# schematic.net
KiCad netlist of a schematic drawn in Altium Designer
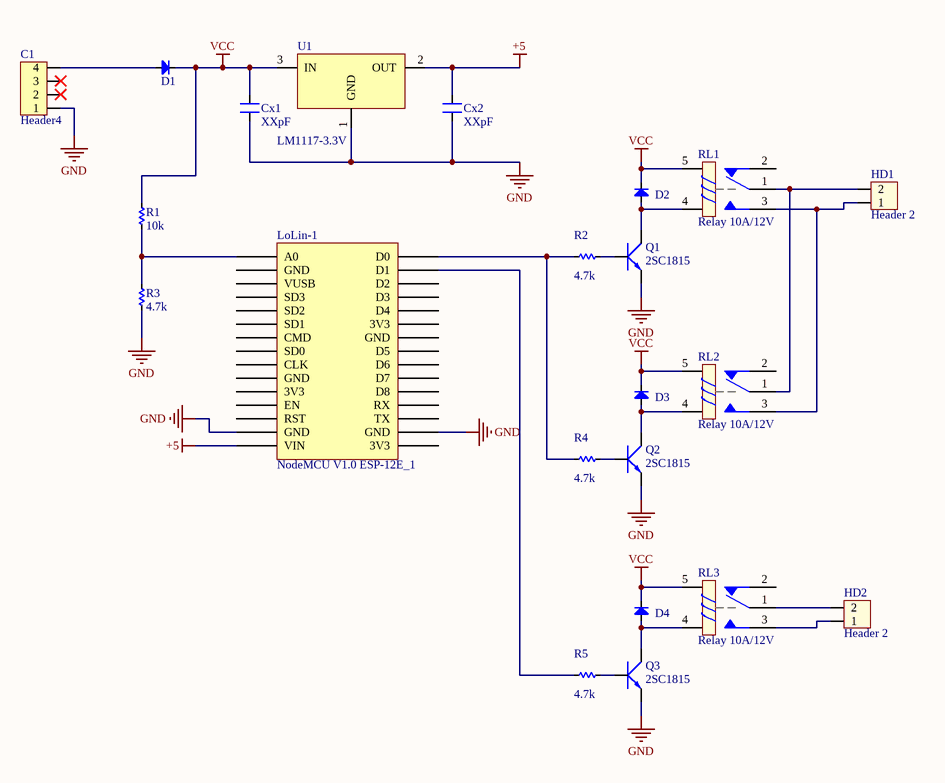
[diagram p0: schematic.SchDoc]

(export (version "E")
  (design (tool "Eeschema 10.0.6"))
  (components
    (comp (ref "C1")
      (value "Header4")
      (footprint "Header4")
      (description "Header IDC, 4 x 1 Pin Vertical 2.54mm Pitch (Non-Boxed, Male)")
      (fields
        (field (name "MANUFACTURER") "Würth Elektronik eiSos GmbH")
        (field (name "PARTNO") "613002143121")
        (field (name "CREATED BY") "Karrer Zheng")
      )
      (libsource (lib "LIBRARY") (part "Header4"))
    )
    (comp (ref "Cx1") (value "XXpF") (footprint "CN-SMD-1206") (libsource (lib "LIBRARY") (part "CN")))
    (comp (ref "Cx2") (value "XXpF") (footprint "CN-SMD-1206") (libsource (lib "LIBRARY") (part "CN")))
    (comp (ref "D1")
      (value "Diode")
      (footprint "DIO-1A-SMALL")
      (description "Default Diode")
      (fields (field (name "PUBLISHER") "Altium Limited"))
      (libsource (lib "LIBRARY") (part "Diode"))
    )
    (comp (ref "D2")
      (value "Diode")
      (footprint "DIO-1A-SMALL")
      (description "Default Diode")
      (fields (field (name "PUBLISHER") "Altium Limited"))
      (libsource (lib "LIBRARY") (part "Diode"))
    )
    (comp (ref "D3")
      (value "Diode")
      (footprint "DIO-1A-SMALL")
      (description "Default Diode")
      (fields (field (name "PUBLISHER") "Altium Limited"))
      (libsource (lib "LIBRARY") (part "Diode"))
    )
    (comp (ref "D4")
      (value "Diode")
      (footprint "DIO-1A-SMALL")
      (description "Default Diode")
      (fields (field (name "PUBLISHER") "Altium Limited"))
      (libsource (lib "LIBRARY") (part "Diode"))
    )
    (comp (ref "HD1")
      (value "Header 2")
      (footprint "HED2")
      (description "Header 2 (Green)")
      (libsource (lib "syhaunguyen") (part "Hed2"))
    )
    (comp (ref "HD2")
      (value "Header 2")
      (footprint "HED2")
      (description "Header 2 (Green)")
      (libsource (lib "syhaunguyen") (part "Hed2"))
    )
    (comp (ref "LoLin-1")
      (value "NodeMCU V1.0 ESP-12E_1")
      (footprint "LoLin NodeMcu V3")
      (description "LoLin NodeMCU V3")
      (libsource (lib "nodemcu") (part "NodeMCU V1.0 ESP-12E_1"))
    )
    (comp (ref "Q1")
      (value "2SC1815")
      (footprint "TO92-123")
      (description "NPN 600mW, ECB")
      (libsource (lib "LIBRARY") (part "2SC1815"))
    )
    (comp (ref "Q2")
      (value "2SC1815")
      (footprint "TO92-123")
      (description "NPN 600mW, ECB")
      (libsource (lib "LIBRARY") (part "2SC1815"))
    )
    (comp (ref "Q3")
      (value "2SC1815")
      (footprint "TO92-123")
      (description "NPN 600mW, ECB")
      (libsource (lib "LIBRARY") (part "2SC1815"))
    )
    (comp (ref "R1")
      (value "10k")
      (footprint "RES-1/4W-SMALL")
      (description "Res")
      (fields
        (field (name "MANUFACTURER") "Generic Components")
        (field (name "PUBLISHER") "Altium Hobart Technology Centre")
      )
      (libsource (lib "LIBRARY") (part "Res"))
    )
    (comp (ref "R2")
      (value "4.7k")
      (footprint "RES-1/4W-SMALL")
      (description "Res")
      (fields
        (field (name "MANUFACTURER") "Generic Components")
        (field (name "PUBLISHER") "Altium Hobart Technology Centre")
      )
      (libsource (lib "LIBRARY") (part "Res"))
    )
    (comp (ref "R3")
      (value "4.7k")
      (footprint "RES-1/4W-SMALL")
      (description "Res")
      (fields
        (field (name "MANUFACTURER") "Generic Components")
        (field (name "PUBLISHER") "Altium Hobart Technology Centre")
      )
      (libsource (lib "LIBRARY") (part "Res"))
    )
    (comp (ref "R4")
      (value "4.7k")
      (footprint "RES-1/4W-SMALL")
      (description "Res")
      (fields
        (field (name "MANUFACTURER") "Generic Components")
        (field (name "PUBLISHER") "Altium Hobart Technology Centre")
      )
      (libsource (lib "LIBRARY") (part "Res"))
    )
    (comp (ref "R5")
      (value "4.7k")
      (footprint "RES-1/4W-SMALL")
      (description "Res")
      (fields
        (field (name "MANUFACTURER") "Generic Components")
        (field (name "PUBLISHER") "Altium Hobart Technology Centre")
      )
      (libsource (lib "LIBRARY") (part "Res"))
    )
    (comp (ref "RL1")
      (value "Relay 10A/12V")
      (footprint "RELAY 5")
      (description "Relay SPDT,10A - 12VDC 5 Pin")
      (libsource (lib "LIBRARY") (part "Relay 5"))
    )
    (comp (ref "RL2")
      (value "Relay 10A/12V")
      (footprint "RELAY 5")
      (description "Relay SPDT,10A - 12VDC 5 Pin")
      (libsource (lib "LIBRARY") (part "Relay 5"))
    )
    (comp (ref "RL3")
      (value "Relay 10A/12V")
      (footprint "RELAY 5")
      (description "Relay SPDT,10A - 12VDC 5 Pin")
      (libsource (lib "LIBRARY") (part "Relay 5"))
    )
    (comp (ref "U1")
      (value "LM1117-3.3V")
      (footprint "SOT223")
      (description "800mA Low-Dropout Linear Regulator")
      (fields (field (name "CREATOR") "Nguyen Ba Bien"))
      (libsource (lib "LIBRARY") (part "LM1117"))
    )
  )
  (nets
    (net (code "1") (name "+5") (class "Default")
      (node (ref "Cx2") (pin "2") (pinfunction "2_2") (pintype "passive"))
      (node (ref "LoLin-1") (pin "VIN") (pinfunction "VIN_VIN") (pintype "passive"))
      (node (ref "U1") (pin "2") (pinfunction "OUT_2") (pintype "passive"))
    )
    (net (code "2") (name "GND") (class "Default")
      (node (ref "C1") (pin "1") (pinfunction "1_1") (pintype "passive"))
      (node (ref "Cx1") (pin "1") (pinfunction "1_1") (pintype "passive"))
      (node (ref "Cx2") (pin "1") (pinfunction "1_1") (pintype "passive"))
      (node (ref "LoLin-1") (pin "GND") (pinfunction "GND_GND") (pintype "passive"))
      (node (ref "Q1") (pin "1") (pinfunction "E_1") (pintype "passive"))
      (node (ref "Q2") (pin "1") (pinfunction "E_1") (pintype "passive"))
      (node (ref "Q3") (pin "1") (pinfunction "E_1") (pintype "passive"))
      (node (ref "R3") (pin "2") (pinfunction "2_2") (pintype "passive"))
      (node (ref "U1") (pin "1") (pinfunction "GND_1") (pintype "passive"))
    )
    (net (code "3") (name "Net-(D1-A)") (class "Default")
      (node (ref "C1") (pin "4") (pinfunction "4_4") (pintype "passive"))
      (node (ref "D1") (pin "1") (pinfunction "A_1") (pintype "passive"))
    )
    (net (code "4") (name "Net-(D2-A)") (class "Default")
      (node (ref "D2") (pin "1") (pinfunction "A_1") (pintype "passive"))
      (node (ref "Q1") (pin "2") (pinfunction "C_2") (pintype "passive"))
      (node (ref "RL1") (pin "4") (pinfunction "4_4") (pintype "passive"))
    )
    (net (code "5") (name "Net-(D3-A)") (class "Default")
      (node (ref "D3") (pin "1") (pinfunction "A_1") (pintype "passive"))
      (node (ref "Q2") (pin "2") (pinfunction "C_2") (pintype "passive"))
      (node (ref "RL2") (pin "4") (pinfunction "4_4") (pintype "passive"))
    )
    (net (code "6") (name "Net-(D4-A)") (class "Default")
      (node (ref "D4") (pin "1") (pinfunction "A_1") (pintype "passive"))
      (node (ref "Q3") (pin "2") (pinfunction "C_2") (pintype "passive"))
      (node (ref "RL3") (pin "4") (pinfunction "4_4") (pintype "passive"))
    )
    (net (code "7") (name "Net-(HD1-Pad1)") (class "Default")
      (node (ref "HD1") (pin "1") (pinfunction "1_1") (pintype "passive"))
      (node (ref "RL1") (pin "3") (pinfunction "3_3") (pintype "passive"))
      (node (ref "RL2") (pin "3") (pinfunction "3_3") (pintype "passive"))
    )
    (net (code "8") (name "Net-(HD1-Pad2)") (class "Default")
      (node (ref "HD1") (pin "2") (pinfunction "2_2") (pintype "passive"))
      (node (ref "RL1") (pin "1") (pinfunction "1_1") (pintype "passive"))
      (node (ref "RL2") (pin "1") (pinfunction "1_1") (pintype "passive"))
    )
    (net (code "9") (name "Net-(HD2-Pad1)") (class "Default")
      (node (ref "HD2") (pin "1") (pinfunction "1_1") (pintype "passive"))
      (node (ref "RL3") (pin "3") (pinfunction "3_3") (pintype "passive"))
    )
    (net (code "10") (name "Net-(HD2-Pad2)") (class "Default")
      (node (ref "HD2") (pin "2") (pinfunction "2_2") (pintype "passive"))
      (node (ref "RL3") (pin "1") (pinfunction "1_1") (pintype "passive"))
    )
    (net (code "11") (name "Net-(LoLin-1-PadA0)") (class "Default")
      (node (ref "LoLin-1") (pin "A0") (pinfunction "A0_A0") (pintype "passive"))
      (node (ref "R1") (pin "2") (pinfunction "2_2") (pintype "passive"))
      (node (ref "R3") (pin "1") (pinfunction "1_1") (pintype "passive"))
    )
    (net (code "12") (name "Net-(LoLin-1-PadD0)") (class "Default")
      (node (ref "LoLin-1") (pin "D0") (pinfunction "D0_D0") (pintype "passive"))
      (node (ref "R2") (pin "2") (pinfunction "2_2") (pintype "passive"))
      (node (ref "R4") (pin "2") (pinfunction "2_2") (pintype "passive"))
    )
    (net (code "13") (name "Net-(LoLin-1-PadD1)") (class "Default")
      (node (ref "LoLin-1") (pin "D1") (pinfunction "D1_D1") (pintype "passive"))
      (node (ref "R5") (pin "2") (pinfunction "2_2") (pintype "passive"))
    )
    (net (code "14") (name "Net-(Q1-B)") (class "Default")
      (node (ref "Q1") (pin "3") (pinfunction "B_3") (pintype "passive"))
      (node (ref "R2") (pin "1") (pinfunction "1_1") (pintype "passive"))
    )
    (net (code "15") (name "Net-(Q2-B)") (class "Default")
      (node (ref "Q2") (pin "3") (pinfunction "B_3") (pintype "passive"))
      (node (ref "R4") (pin "1") (pinfunction "1_1") (pintype "passive"))
    )
    (net (code "16") (name "Net-(Q3-B)") (class "Default")
      (node (ref "Q3") (pin "3") (pinfunction "B_3") (pintype "passive"))
      (node (ref "R5") (pin "1") (pinfunction "1_1") (pintype "passive"))
    )
    (net (code "17") (name "VCC") (class "Default")
      (node (ref "Cx1") (pin "2") (pinfunction "2_2") (pintype "passive"))
      (node (ref "D1") (pin "2") (pinfunction "K_2") (pintype "passive"))
      (node (ref "D2") (pin "2") (pinfunction "K_2") (pintype "passive"))
      (node (ref "D3") (pin "2") (pinfunction "K_2") (pintype "passive"))
      (node (ref "D4") (pin "2") (pinfunction "K_2") (pintype "passive"))
      (node (ref "R1") (pin "1") (pinfunction "1_1") (pintype "passive"))
      (node (ref "RL1") (pin "5") (pinfunction "5_5") (pintype "passive"))
      (node (ref "RL2") (pin "5") (pinfunction "5_5") (pintype "passive"))
      (node (ref "RL3") (pin "5") (pinfunction "5_5") (pintype "passive"))
      (node (ref "U1") (pin "3") (pinfunction "IN_3") (pintype "passive"))
    )
    (net (code "18") (name "unconnected-(C1-Pad2)") (class "Default")
      (node (ref "C1") (pin "2") (pinfunction "2_2") (pintype "passive+no_connect"))
    )
    (net (code "19") (name "unconnected-(C1-Pad3)") (class "Default")
      (node (ref "C1") (pin "3") (pinfunction "3_3") (pintype "passive+no_connect"))
    )
    (net (code "20") (name "unconnected-(LoLin-1-Pad3V3)") (class "Default")
      (node (ref "LoLin-1") (pin "3V3") (pinfunction "3V3_3V3") (pintype "passive"))
    )
    (net (code "21") (name "unconnected-(LoLin-1-Pad3V3)_1") (class "Default")
      (node (ref "LoLin-1") (pin "3V3") (pinfunction "3V3_3V3") (pintype "passive"))
    )
    (net (code "22") (name "unconnected-(LoLin-1-Pad3V3)_2") (class "Default")
      (node (ref "LoLin-1") (pin "3V3") (pinfunction "3V3_3V3") (pintype "passive"))
    )
    (net (code "23") (name "unconnected-(LoLin-1-PadCLK)") (class "Default")
      (node (ref "LoLin-1") (pin "CLK") (pinfunction "CLK_CLK") (pintype "passive"))
    )
    (net (code "24") (name "unconnected-(LoLin-1-PadCMD)") (class "Default")
      (node (ref "LoLin-1") (pin "CMD") (pinfunction "CMD_CMD") (pintype "passive"))
    )
    (net (code "25") (name "unconnected-(LoLin-1-PadD2)") (class "Default")
      (node (ref "LoLin-1") (pin "D2") (pinfunction "D2_D2") (pintype "passive"))
    )
    (net (code "26") (name "unconnected-(LoLin-1-PadD3)") (class "Default")
      (node (ref "LoLin-1") (pin "D3") (pinfunction "D3_D3") (pintype "passive"))
    )
    (net (code "27") (name "unconnected-(LoLin-1-PadD4)") (class "Default")
      (node (ref "LoLin-1") (pin "D4") (pinfunction "D4_D4") (pintype "passive"))
    )
    (net (code "28") (name "unconnected-(LoLin-1-PadD5)") (class "Default")
      (node (ref "LoLin-1") (pin "D5") (pinfunction "D5_D5") (pintype "passive"))
    )
    (net (code "29") (name "unconnected-(LoLin-1-PadD6)") (class "Default")
      (node (ref "LoLin-1") (pin "D6") (pinfunction "D6_D6") (pintype "passive"))
    )
    (net (code "30") (name "unconnected-(LoLin-1-PadD7)") (class "Default")
      (node (ref "LoLin-1") (pin "D7") (pinfunction "D7_D7") (pintype "passive"))
    )
    (net (code "31") (name "unconnected-(LoLin-1-PadD8)") (class "Default")
      (node (ref "LoLin-1") (pin "D8") (pinfunction "D8_D8") (pintype "passive"))
    )
    (net (code "32") (name "unconnected-(LoLin-1-PadEN)") (class "Default")
      (node (ref "LoLin-1") (pin "EN") (pinfunction "EN_EN") (pintype "passive"))
    )
    (net (code "33") (name "unconnected-(LoLin-1-PadGND)") (class "Default")
      (node (ref "LoLin-1") (pin "GND") (pinfunction "GND_GND") (pintype "passive"))
    )
    (net (code "34") (name "unconnected-(LoLin-1-PadGND)_1") (class "Default")
      (node (ref "LoLin-1") (pin "GND") (pinfunction "GND_GND") (pintype "passive"))
    )
    (net (code "35") (name "unconnected-(LoLin-1-PadGND)_2") (class "Default")
      (node (ref "LoLin-1") (pin "GND") (pinfunction "GND_GND") (pintype "passive"))
    )
    (net (code "36") (name "unconnected-(LoLin-1-PadRST)") (class "Default")
      (node (ref "LoLin-1") (pin "RST") (pinfunction "RST_RST") (pintype "passive"))
    )
    (net (code "37") (name "unconnected-(LoLin-1-PadRX)") (class "Default")
      (node (ref "LoLin-1") (pin "RX") (pinfunction "RX_RX") (pintype "passive"))
    )
    (net (code "38") (name "unconnected-(LoLin-1-PadSD0)") (class "Default")
      (node (ref "LoLin-1") (pin "SD0") (pinfunction "SD0_SD0") (pintype "passive"))
    )
    (net (code "39") (name "unconnected-(LoLin-1-PadSD1)") (class "Default")
      (node (ref "LoLin-1") (pin "SD1") (pinfunction "SD1_SD1") (pintype "passive"))
    )
    (net (code "40") (name "unconnected-(LoLin-1-PadSD2)") (class "Default")
      (node (ref "LoLin-1") (pin "SD2") (pinfunction "SD2_SD2") (pintype "passive"))
    )
    (net (code "41") (name "unconnected-(LoLin-1-PadSD3)") (class "Default")
      (node (ref "LoLin-1") (pin "SD3") (pinfunction "SD3_SD3") (pintype "passive"))
    )
    (net (code "42") (name "unconnected-(LoLin-1-PadTX)") (class "Default")
      (node (ref "LoLin-1") (pin "TX") (pinfunction "TX_TX") (pintype "passive"))
    )
    (net (code "43") (name "unconnected-(LoLin-1-PadVUSB)") (class "Default")
      (node (ref "LoLin-1") (pin "VUSB") (pinfunction "VUSB_VUSB") (pintype "passive"))
    )
    (net (code "44") (name "unconnected-(RL1-Pad2)") (class "Default")
      (node (ref "RL1") (pin "2") (pinfunction "2_2") (pintype "passive"))
    )
    (net (code "45") (name "unconnected-(RL2-Pad2)") (class "Default")
      (node (ref "RL2") (pin "2") (pinfunction "2_2") (pintype "passive"))
    )
    (net (code "46") (name "unconnected-(RL3-Pad2)") (class "Default")
      (node (ref "RL3") (pin "2") (pinfunction "2_2") (pintype "passive"))
    )
  )
)
